# AEBS_component.net
KiCad netlist of a schematic drawn in Altium Designer
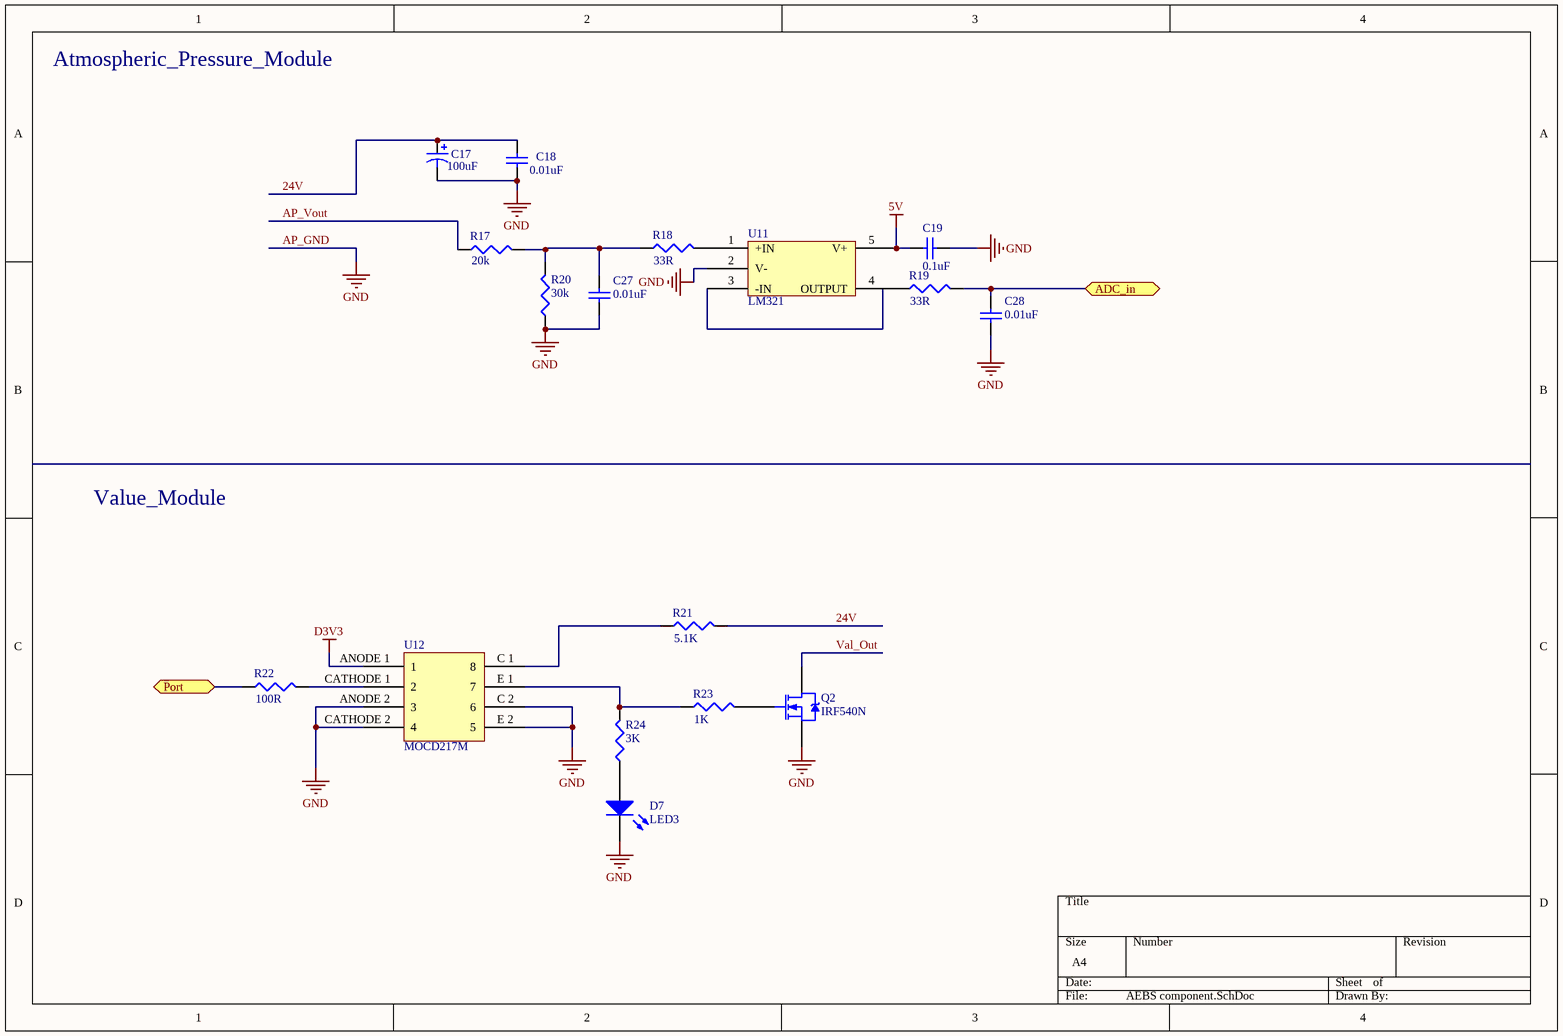
[diagram p0: AEBS component.SchDoc]

(export (version "E")
  (design (tool "Eeschema 10.0.6"))
  (components
    (comp (ref "C17")
      (value "100uF")
      (footprint "C0805")
      (description "Polarized Capacitor (Surface Mount)")
      (fields (field (name "Comment") "Cap Pol3") (field (name "PUBLISHER") "Altium Limited"))
      (libsource (lib "Miscellaneous Devices") (part "Cap Pol3"))
    )
    (comp (ref "C18")
      (value "0.01uF")
      (footprint "C1206")
      (description "Capacitor (Semiconductor SIM Model)")
      (fields (field (name "Comment") "Cap Semi") (field (name "PUBLISHER") "Altium Limited"))
      (libsource (lib "Miscellaneous Devices") (part "Cap Semi"))
    )
    (comp (ref "C19")
      (value "0.1uF")
      (footprint "1608[0603]")
      (description "Capacitor (Semiconductor SIM Model)")
      (fields (field (name "Comment") "Cap Semi") (field (name "PUBLISHER") "Altium Limited"))
      (libsource (lib "Miscellaneous Devices") (part "Cap Semi"))
    )
    (comp (ref "C27")
      (value "0.01uF")
      (footprint "1608[0603]")
      (description "Capacitor (Semiconductor SIM Model)")
      (fields (field (name "Comment") "Cap Semi") (field (name "PUBLISHER") "Altium Limited"))
      (libsource (lib "Miscellaneous Devices") (part "Cap Semi"))
    )
    (comp (ref "C28")
      (value "0.01uF")
      (footprint "1608[0603]")
      (description "Capacitor (Semiconductor SIM Model)")
      (fields (field (name "Comment") "Cap Semi") (field (name "PUBLISHER") "Altium Limited"))
      (libsource (lib "Miscellaneous Devices") (part "Cap Semi"))
    )
    (comp (ref "D7")
      (value "LED3")
      (footprint "3.5X2.8X1.9")
      (description "Typical BLUE SiC LED")
      (fields (field (name "PUBLISHER") "Altium Limited"))
      (libsource (lib "Miscellaneous Devices") (part "LED3"))
    )
    (comp (ref "Q2")
      (value "IRF540N")
      (footprint "TO-220AB")
      (description "N-Channel Power MOSFET")
      (fields (field (name "PUBLISHER") "Altium Limited"))
      (libsource (lib "Miscellaneous Devices") (part "NMOS-2"))
    )
    (comp (ref "R17")
      (value "20k")
      (footprint "J1-0603")
      (description "Resistor")
      (fields (field (name "Comment") "Res3") (field (name "PUBLISHER") "Altium Limited"))
      (libsource (lib "Miscellaneous Devices") (part "Res3"))
    )
    (comp (ref "R18")
      (value "33R")
      (footprint "J1-0603")
      (description "Resistor")
      (fields (field (name "Comment") "Res3") (field (name "PUBLISHER") "Altium Limited"))
      (libsource (lib "Miscellaneous Devices") (part "Res3"))
    )
    (comp (ref "R19")
      (value "33R")
      (footprint "J1-0603")
      (description "Resistor")
      (fields (field (name "Comment") "Res3") (field (name "PUBLISHER") "Altium Limited"))
      (libsource (lib "Miscellaneous Devices") (part "Res3"))
    )
    (comp (ref "R20")
      (value "30k")
      (footprint "J1-0603")
      (description "Resistor")
      (fields (field (name "Comment") "Res3") (field (name "PUBLISHER") "Altium Limited"))
      (libsource (lib "Miscellaneous Devices") (part "Res3"))
    )
    (comp (ref "R21")
      (value "5.1K")
      (footprint "J1-0603")
      (description "Resistor")
      (fields (field (name "Comment") "Res3") (field (name "PUBLISHER") "Altium Limited"))
      (libsource (lib "Miscellaneous Devices") (part "Res3"))
    )
    (comp (ref "R22")
      (value "100R")
      (footprint "J1-0603")
      (description "Resistor")
      (fields (field (name "Comment") "Res3") (field (name "PUBLISHER") "Altium Limited"))
      (libsource (lib "Miscellaneous Devices") (part "Res3"))
    )
    (comp (ref "R23")
      (value "1K")
      (footprint "J1-0603")
      (description "Resistor")
      (fields (field (name "Comment") "Res3") (field (name "PUBLISHER") "Altium Limited"))
      (libsource (lib "Miscellaneous Devices") (part "Res3"))
    )
    (comp (ref "R24")
      (value "3K")
      (footprint "J1-0603")
      (description "Resistor")
      (fields (field (name "Comment") "Res3") (field (name "PUBLISHER") "Altium Limited"))
      (libsource (lib "Miscellaneous Devices") (part "Res3"))
    )
    (comp (ref "U11") (value "LM321") (footprint "hg:LM321") (libsource (lib "hg") (part "LM321")))
    (comp (ref "U12") (value "MOCD217M") (footprint "hg:MOCD217M") (libsource (lib "hg") (part "MOCD217M")))
  )
  (nets
    (net (code "1") (name "/24V") (class "Default")
      (node (ref "C17") (pin "1") (pinfunction "1_1") (pintype "passive"))
      (node (ref "C18") (pin "1") (pinfunction "1_1") (pintype "passive"))
      (node (ref "R21") (pin "2") (pinfunction "2_2") (pintype "passive"))
    )
    (net (code "2") (name "/ADC_in") (class "Default")
      (node (ref "C28") (pin "2") (pinfunction "2_2") (pintype "passive"))
      (node (ref "R19") (pin "2") (pinfunction "2_2") (pintype "passive"))
    )
    (net (code "3") (name "/AP_Vout") (class "Default")
      (node (ref "R17") (pin "1") (pinfunction "1_1") (pintype "passive"))
    )
    (net (code "4") (name "/Port") (class "Default")
      (node (ref "R22") (pin "1") (pinfunction "1_1") (pintype "passive"))
    )
    (net (code "5") (name "/Val_Out") (class "Default")
      (node (ref "Q2") (pin "2") (pinfunction "D_2") (pintype "passive"))
    )
    (net (code "6") (name "5V") (class "Default")
      (node (ref "C19") (pin "2") (pinfunction "2_2") (pintype "passive"))
      (node (ref "U11") (pin "5") (pinfunction "V+_5") (pintype "passive"))
    )
    (net (code "7") (name "D3V3") (class "Default")
      (node (ref "U12") (pin "ANODE_1") (pinfunction "1_ANODE_1") (pintype "passive"))
    )
    (net (code "8") (name "GND") (class "Default")
      (node (ref "C17") (pin "2") (pinfunction "2_2") (pintype "passive"))
      (node (ref "C18") (pin "2") (pinfunction "2_2") (pintype "passive"))
      (node (ref "C19") (pin "1") (pinfunction "1_1") (pintype "passive"))
      (node (ref "C27") (pin "1") (pinfunction "1_1") (pintype "passive"))
      (node (ref "C28") (pin "1") (pinfunction "1_1") (pintype "passive"))
      (node (ref "D7") (pin "2") (pinfunction "K_2") (pintype "passive"))
      (node (ref "Q2") (pin "3") (pinfunction "S_3") (pintype "passive"))
      (node (ref "R20") (pin "1") (pinfunction "1_1") (pintype "passive"))
      (node (ref "U11") (pin "2") (pinfunction "V-_2") (pintype "passive"))
      (node (ref "U12") (pin "ANODE_2") (pinfunction "3_ANODE_2") (pintype "passive"))
      (node (ref "U12") (pin "CATHODE_2") (pinfunction "4_CATHODE_2") (pintype "passive"))
      (node (ref "U12") (pin "C_2") (pinfunction "6_C_2") (pintype "passive"))
      (node (ref "U12") (pin "E_2") (pinfunction "5_E_2") (pintype "passive"))
    )
    (net (code "9") (name "Net-(C27-Pad2)") (class "Default")
      (node (ref "C27") (pin "2") (pinfunction "2_2") (pintype "passive"))
      (node (ref "R17") (pin "2") (pinfunction "2_2") (pintype "passive"))
      (node (ref "R18") (pin "1") (pinfunction "1_1") (pintype "passive"))
      (node (ref "R20") (pin "2") (pinfunction "2_2") (pintype "passive"))
    )
    (net (code "10") (name "Net-(D7-A)") (class "Default")
      (node (ref "D7") (pin "1") (pinfunction "A_1") (pintype "passive"))
      (node (ref "R24") (pin "1") (pinfunction "1_1") (pintype "passive"))
    )
    (net (code "11") (name "Net-(Q2-G)") (class "Default")
      (node (ref "Q2") (pin "1") (pinfunction "G_1") (pintype "passive"))
      (node (ref "R23") (pin "2") (pinfunction "2_2") (pintype "passive"))
    )
    (net (code "12") (name "Net-(U11-+IN)") (class "Default")
      (node (ref "R18") (pin "2") (pinfunction "2_2") (pintype "passive"))
      (node (ref "U11") (pin "1") (pinfunction "+IN_1") (pintype "passive"))
    )
    (net (code "13") (name "Net-(U11-OUTPUT)") (class "Default")
      (node (ref "R19") (pin "1") (pinfunction "1_1") (pintype "passive"))
      (node (ref "U11") (pin "4") (pinfunction "OUTPUT_4") (pintype "passive"))
    )
    (net (code "14") (name "Net-(U12-2)") (class "Default")
      (node (ref "R22") (pin "2") (pinfunction "2_2") (pintype "passive"))
      (node (ref "U12") (pin "CATHODE_1") (pinfunction "2_CATHODE_1") (pintype "passive"))
    )
    (net (code "15") (name "Net-(U12-7)") (class "Default")
      (node (ref "R23") (pin "1") (pinfunction "1_1") (pintype "passive"))
      (node (ref "R24") (pin "2") (pinfunction "2_2") (pintype "passive"))
      (node (ref "U12") (pin "E_1") (pinfunction "7_E_1") (pintype "passive"))
    )
    (net (code "16") (name "Net-(U12-8)") (class "Default")
      (node (ref "R21") (pin "1") (pinfunction "1_1") (pintype "passive"))
      (node (ref "U12") (pin "C_1") (pinfunction "8_C_1") (pintype "passive"))
    )
    (net (code "17") (name "unconnected-(U11--IN-Pad3)") (class "Default")
      (node (ref "U11") (pin "3") (pinfunction "-IN_3") (pintype "passive"))
    )
  )
)
